# lijnvolger_plan_B.net
KiCad netlist of a schematic drawn in EasyEDA
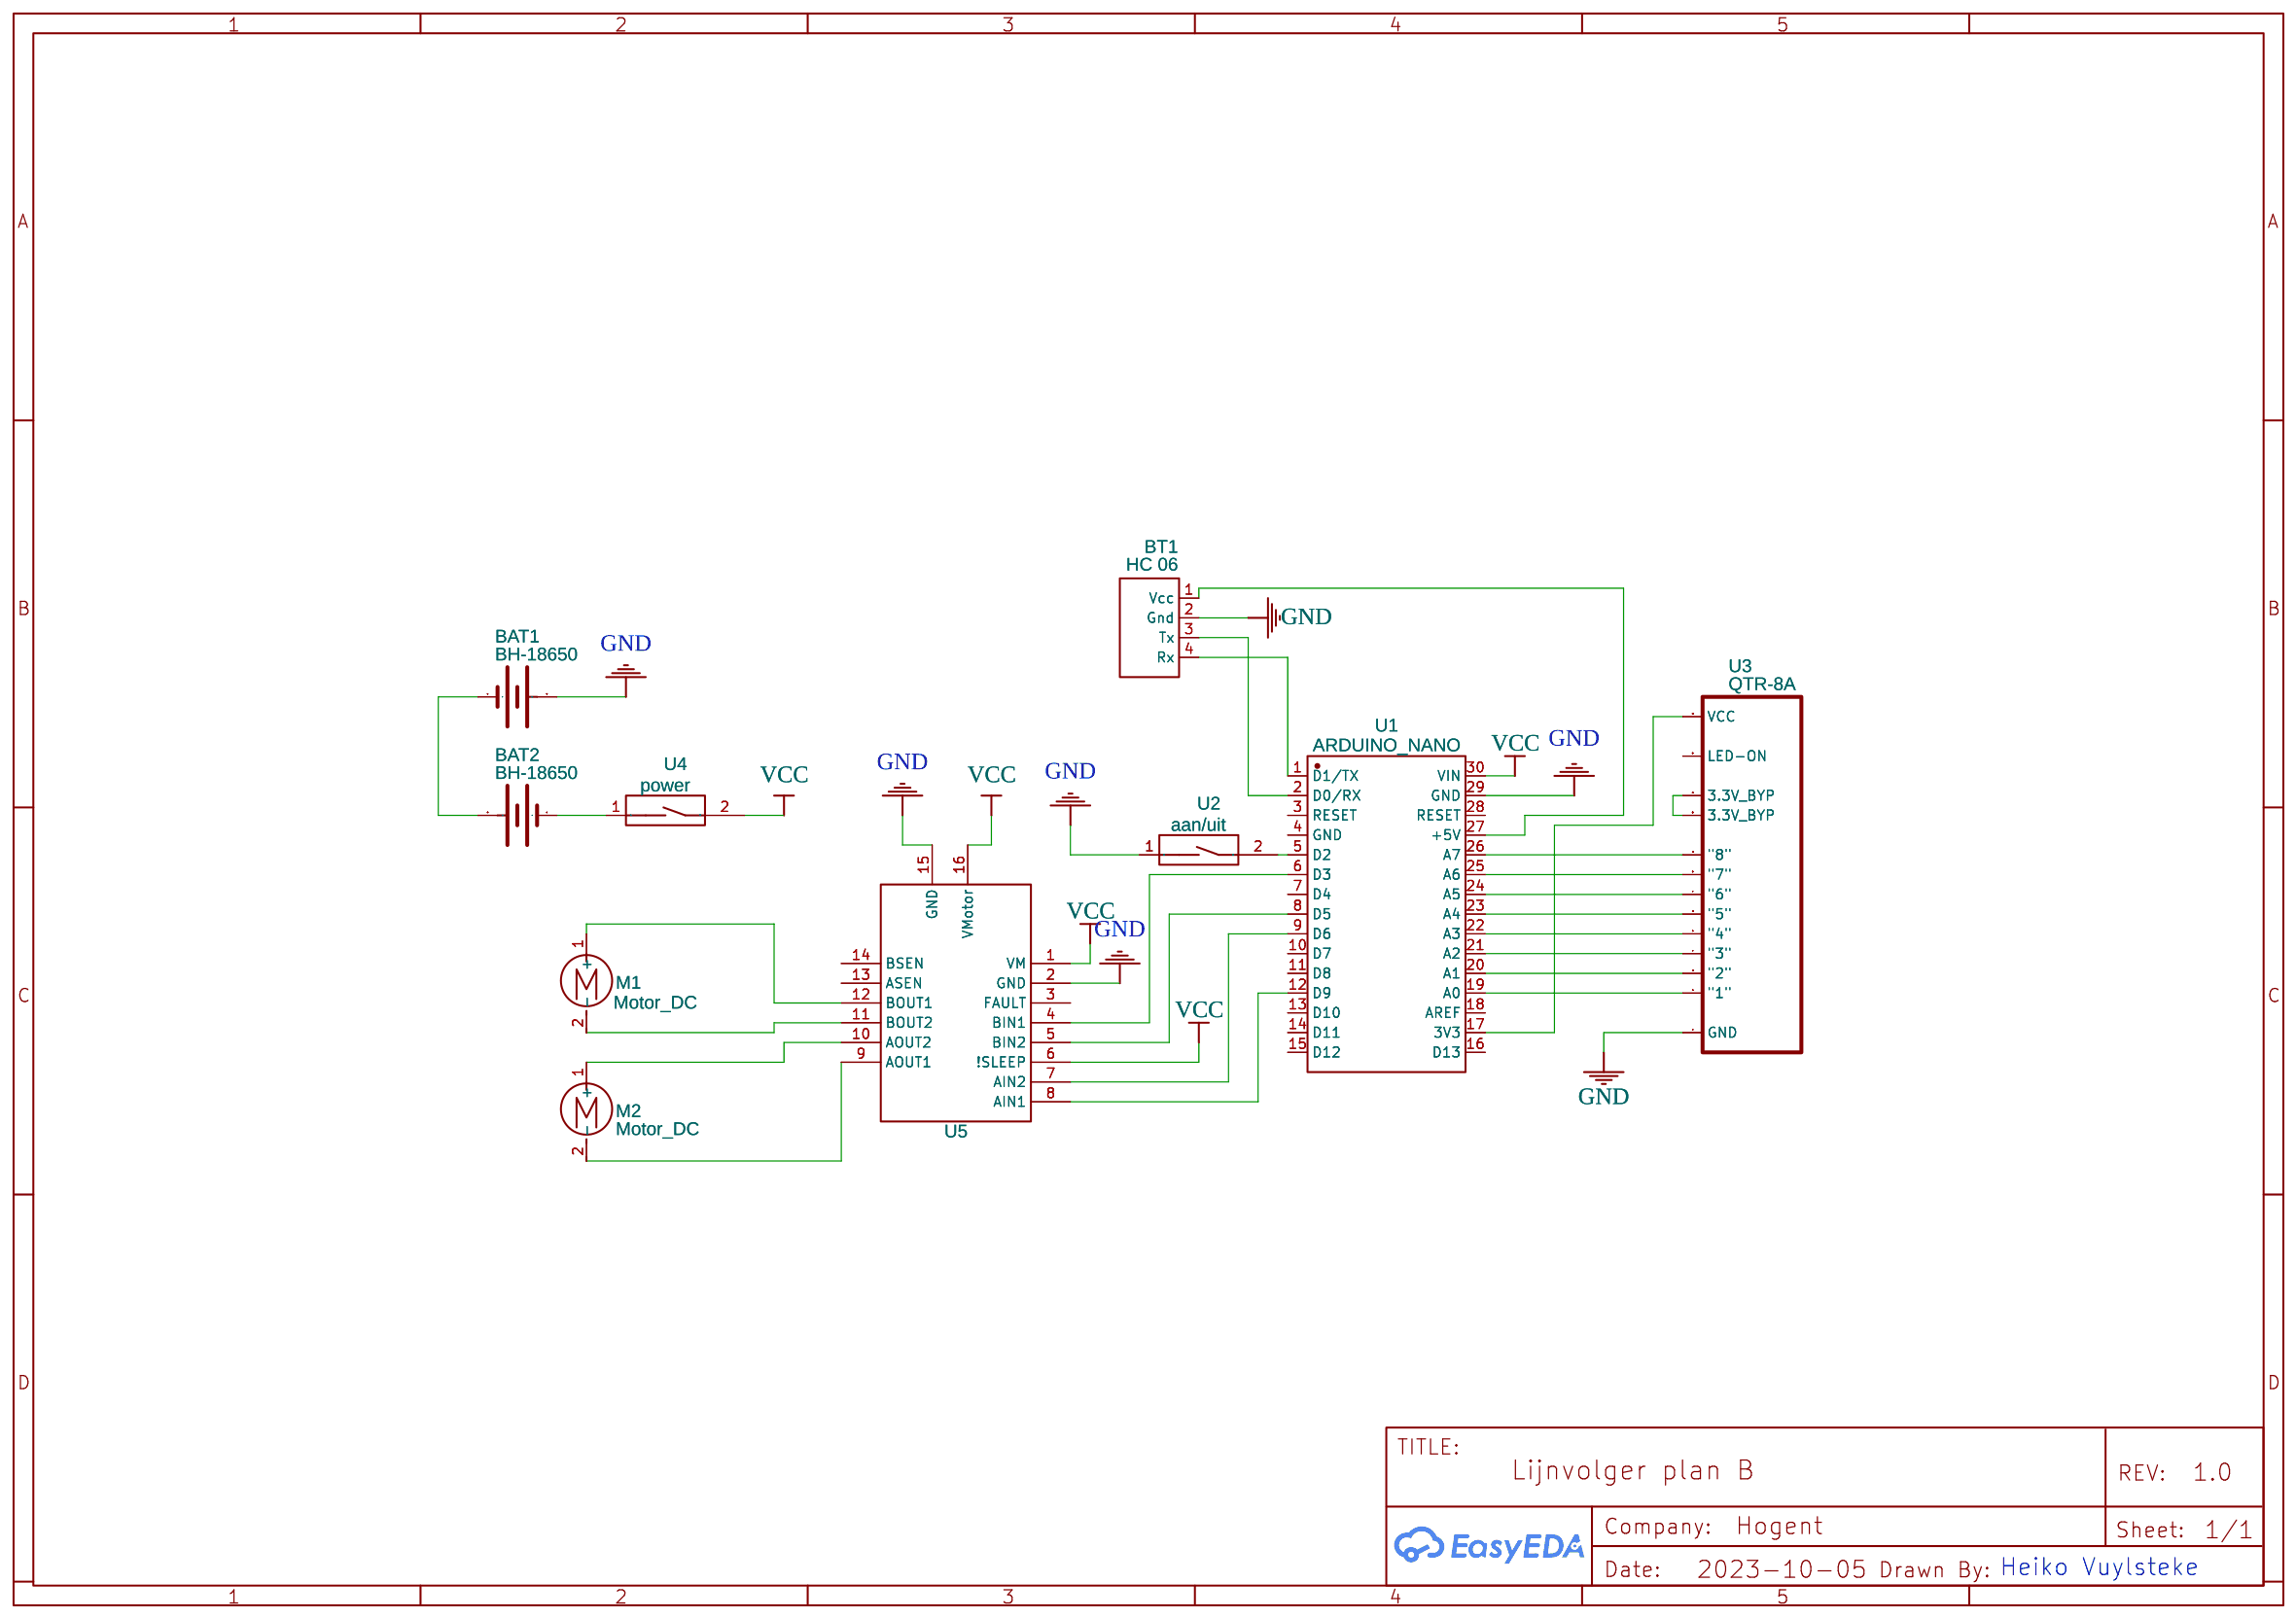
[diagram p0: schematic sheet]

(export (version "E")
  (design (tool "Eeschema 10.0.6"))
  (components
    (comp (ref "BAT1") (value "BH-18650") (libsource (lib "") (part "BH-18650")))
    (comp (ref "BAT2") (value "BH-18650") (libsource (lib "") (part "BH-18650_1")))
    (comp (ref "BT1") (value "HC 06") (libsource (lib "") (part "HC 06")))
    (comp (ref "M1") (value "Motor_DC") (libsource (lib "") (part "Motor_DC")))
    (comp (ref "M2") (value "Motor_DC") (libsource (lib "") (part "Motor_DC")))
    (comp (ref "U1") (value "ARDUINO_NANO") (libsource (lib "") (part "ARDUINO_NANO")))
    (comp (ref "U2")
      (value "aan/uit")
      (fields (field (name "Manufacturer Part") "DIP switchEI-08") (field (name "Manufacturer") "DIP"))
      (libsource (lib "") (part "SWITCH"))
    )
    (comp (ref "U3")
      (value "QTR-8A")
      (fields (field (name "Manufacturer") "Pololu"))
      (libsource (lib "") (part "QTR-8A"))
    )
    (comp (ref "U4")
      (value "power")
      (fields (field (name "Manufacturer Part") "DIP switchEI-08") (field (name "Manufacturer") "DIP"))
      (libsource (lib "") (part "SWITCH"))
    )
    (comp (ref "U5")
      (value "~")
      (fields (field (name "Manufacturer Part") "Adafruit"))
      (libsource (lib "") (part "Adafruit DRV8833 Breakout"))
    )
  )
  (nets
    (net (code "1") (name "GND") (class "Default")
      (node (ref "BAT1") (pin "2") (pinfunction "+_2") (pintype "passive"))
      (node (ref "BT1") (pin "2") (pinfunction "Gnd_2") (pintype "unspecified"))
      (node (ref "U1") (pin "29") (pinfunction "GND_29") (pintype "unspecified"))
      (node (ref "U2") (pin "1") (pinfunction "1_1") (pintype "unspecified"))
      (node (ref "U3") (pin "1") (pinfunction "GND_1") (pintype "unspecified"))
      (node (ref "U5") (pin "15") (pinfunction "GND_15") (pintype "unspecified"))
      (node (ref "U5") (pin "2") (pinfunction "GND_2") (pintype "unspecified"))
    )
    (net (code "2") (name "Net-(BAT1--)") (class "Default")
      (node (ref "BAT1") (pin "1") (pinfunction "-_1") (pintype "passive"))
      (node (ref "BAT2") (pin "2") (pinfunction "+_2") (pintype "passive"))
    )
    (net (code "3") (name "Net-(BAT2--)") (class "Default")
      (node (ref "BAT2") (pin "1") (pinfunction "-_1") (pintype "passive"))
      (node (ref "U4") (pin "1") (pinfunction "1_1") (pintype "unspecified"))
    )
    (net (code "4") (name "Net-(BT1-Rx)") (class "Default")
      (node (ref "BT1") (pin "4") (pinfunction "Rx_4") (pintype "unspecified"))
      (node (ref "U1") (pin "1") (pinfunction "D1/TX_1") (pintype "unspecified"))
    )
    (net (code "5") (name "Net-(BT1-Tx)") (class "Default")
      (node (ref "BT1") (pin "3") (pinfunction "Tx_3") (pintype "unspecified"))
      (node (ref "U1") (pin "2") (pinfunction "D0/RX_2") (pintype "unspecified"))
    )
    (net (code "6") (name "Net-(BT1-Vcc)") (class "Default")
      (node (ref "BT1") (pin "1") (pinfunction "Vcc_1") (pintype "unspecified"))
      (node (ref "U1") (pin "27") (pinfunction "+5V_27") (pintype "unspecified"))
    )
    (net (code "7") (name "Net-(M1-+)") (class "Default")
      (node (ref "M1") (pin "1") (pinfunction "+_1") (pintype "unspecified"))
      (node (ref "U5") (pin "12") (pinfunction "BOUT1_12") (pintype "unspecified"))
    )
    (net (code "8") (name "Net-(M1--)") (class "Default")
      (node (ref "M1") (pin "2") (pinfunction "-_2") (pintype "unspecified"))
      (node (ref "U5") (pin "11") (pinfunction "BOUT2_11") (pintype "unspecified"))
    )
    (net (code "9") (name "Net-(M2-+)") (class "Default")
      (node (ref "M2") (pin "1") (pinfunction "+_1") (pintype "unspecified"))
      (node (ref "U5") (pin "10") (pinfunction "AOUT2_10") (pintype "unspecified"))
    )
    (net (code "10") (name "Net-(M2--)") (class "Default")
      (node (ref "M2") (pin "2") (pinfunction "-_2") (pintype "unspecified"))
      (node (ref "U5") (pin "9") (pinfunction "AOUT1_9") (pintype "unspecified"))
    )
    (net (code "11") (name "Net-(U1-3V3)") (class "Default")
      (node (ref "U1") (pin "17") (pinfunction "3V3_17") (pintype "unspecified"))
      (node (ref "U3") (pin "12") (pinfunction "VCC_12") (pintype "unspecified"))
    )
    (net (code "12") (name "Net-(U1-A0)") (class "Default")
      (node (ref "U1") (pin "19") (pinfunction "A0_19") (pintype "unspecified"))
      (node (ref "U3") (pin "2") (pinfunction "\"1\"_2") (pintype "unspecified"))
    )
    (net (code "13") (name "Net-(U1-A1)") (class "Default")
      (node (ref "U1") (pin "20") (pinfunction "A1_20") (pintype "unspecified"))
      (node (ref "U3") (pin "3") (pinfunction "\"2\"_3") (pintype "unspecified"))
    )
    (net (code "14") (name "Net-(U1-A2)") (class "Default")
      (node (ref "U1") (pin "21") (pinfunction "A2_21") (pintype "unspecified"))
      (node (ref "U3") (pin "4") (pinfunction "\"3\"_4") (pintype "unspecified"))
    )
    (net (code "15") (name "Net-(U1-A3)") (class "Default")
      (node (ref "U1") (pin "22") (pinfunction "A3_22") (pintype "unspecified"))
      (node (ref "U3") (pin "5") (pinfunction "\"4\"_5") (pintype "unspecified"))
    )
    (net (code "16") (name "Net-(U1-A4)") (class "Default")
      (node (ref "U1") (pin "23") (pinfunction "A4_23") (pintype "unspecified"))
      (node (ref "U3") (pin "6") (pinfunction "\"5\"_6") (pintype "unspecified"))
    )
    (net (code "17") (name "Net-(U1-A5)") (class "Default")
      (node (ref "U1") (pin "24") (pinfunction "A5_24") (pintype "unspecified"))
      (node (ref "U3") (pin "7") (pinfunction "\"6\"_7") (pintype "unspecified"))
    )
    (net (code "18") (name "Net-(U1-A6)") (class "Default")
      (node (ref "U1") (pin "25") (pinfunction "A6_25") (pintype "unspecified"))
      (node (ref "U3") (pin "8") (pinfunction "\"7\"_8") (pintype "unspecified"))
    )
    (net (code "19") (name "Net-(U1-A7)") (class "Default")
      (node (ref "U1") (pin "26") (pinfunction "A7_26") (pintype "unspecified"))
      (node (ref "U3") (pin "9") (pinfunction "\"8\"_9") (pintype "unspecified"))
    )
    (net (code "20") (name "Net-(U1-D2)") (class "Default")
      (node (ref "U1") (pin "5") (pinfunction "D2_5") (pintype "unspecified"))
      (node (ref "U2") (pin "2") (pinfunction "2_2") (pintype "unspecified"))
    )
    (net (code "21") (name "Net-(U1-D3)") (class "Default")
      (node (ref "U1") (pin "6") (pinfunction "D3_6") (pintype "unspecified"))
      (node (ref "U5") (pin "4") (pinfunction "BIN1_4") (pintype "unspecified"))
    )
    (net (code "22") (name "Net-(U1-D5)") (class "Default")
      (node (ref "U1") (pin "8") (pinfunction "D5_8") (pintype "unspecified"))
      (node (ref "U5") (pin "5") (pinfunction "BIN2_5") (pintype "unspecified"))
    )
    (net (code "23") (name "Net-(U1-D6)") (class "Default")
      (node (ref "U1") (pin "9") (pinfunction "D6_9") (pintype "unspecified"))
      (node (ref "U5") (pin "7") (pinfunction "AIN2_7") (pintype "unspecified"))
    )
    (net (code "24") (name "Net-(U1-D9)") (class "Default")
      (node (ref "U1") (pin "12") (pinfunction "D9_12") (pintype "unspecified"))
      (node (ref "U5") (pin "8") (pinfunction "AIN1_8") (pintype "unspecified"))
    )
    (net (code "25") (name "Net-(U3-3.3V_BYP-Pad10)") (class "Default")
      (node (ref "U3") (pin "10") (pinfunction "3.3V_BYP_10") (pintype "unspecified"))
      (node (ref "U3") (pin "11") (pinfunction "3.3V_BYP_11") (pintype "unspecified"))
    )
    (net (code "26") (name "VCC") (class "Default")
      (node (ref "U1") (pin "30") (pinfunction "VIN_30") (pintype "unspecified"))
      (node (ref "U4") (pin "2") (pinfunction "2_2") (pintype "unspecified"))
      (node (ref "U5") (pin "1") (pinfunction "VM_1") (pintype "unspecified"))
      (node (ref "U5") (pin "16") (pinfunction "VMotor_16") (pintype "unspecified"))
      (node (ref "U5") (pin "6") (pinfunction "!SLEEP_6") (pintype "unspecified"))
    )
    (net (code "27") (name "unconnected-(U1-AREF-Pad18)") (class "Default")
      (node (ref "U1") (pin "18") (pinfunction "AREF_18") (pintype "unspecified"))
    )
    (net (code "28") (name "unconnected-(U1-D4-Pad7)") (class "Default")
      (node (ref "U1") (pin "7") (pinfunction "D4_7") (pintype "unspecified"))
    )
    (net (code "29") (name "unconnected-(U1-D7-Pad10)") (class "Default")
      (node (ref "U1") (pin "10") (pinfunction "D7_10") (pintype "unspecified"))
    )
    (net (code "30") (name "unconnected-(U1-D8-Pad11)") (class "Default")
      (node (ref "U1") (pin "11") (pinfunction "D8_11") (pintype "unspecified"))
    )
    (net (code "31") (name "unconnected-(U1-D10-Pad13)") (class "Default")
      (node (ref "U1") (pin "13") (pinfunction "D10_13") (pintype "unspecified"))
    )
    (net (code "32") (name "unconnected-(U1-D11-Pad14)") (class "Default")
      (node (ref "U1") (pin "14") (pinfunction "D11_14") (pintype "unspecified"))
    )
    (net (code "33") (name "unconnected-(U1-D12-Pad15)") (class "Default")
      (node (ref "U1") (pin "15") (pinfunction "D12_15") (pintype "unspecified"))
    )
    (net (code "34") (name "unconnected-(U1-D13-Pad16)") (class "Default")
      (node (ref "U1") (pin "16") (pinfunction "D13_16") (pintype "unspecified"))
    )
    (net (code "35") (name "unconnected-(U1-GND-Pad4)") (class "Default")
      (node (ref "U1") (pin "4") (pinfunction "GND_4") (pintype "unspecified"))
    )
    (net (code "36") (name "unconnected-(U1-RESET-Pad3)") (class "Default")
      (node (ref "U1") (pin "3") (pinfunction "RESET_3") (pintype "unspecified"))
    )
    (net (code "37") (name "unconnected-(U1-RESET-Pad28)") (class "Default")
      (node (ref "U1") (pin "28") (pinfunction "RESET_28") (pintype "unspecified"))
    )
    (net (code "38") (name "unconnected-(U3-LED-ON-Pad12)") (class "Default")
      (node (ref "U3") (pin "12") (pinfunction "LED-ON_12") (pintype "unspecified"))
    )
    (net (code "39") (name "unconnected-(U5-ASEN-Pad13)") (class "Default")
      (node (ref "U5") (pin "13") (pinfunction "ASEN_13") (pintype "unspecified"))
    )
    (net (code "40") (name "unconnected-(U5-BSEN-Pad14)") (class "Default")
      (node (ref "U5") (pin "14") (pinfunction "BSEN_14") (pintype "unspecified"))
    )
    (net (code "41") (name "unconnected-(U5-FAULT-Pad3)") (class "Default")
      (node (ref "U5") (pin "3") (pinfunction "FAULT_3") (pintype "unspecified"))
    )
  )
)
